# untitled.net
KiCad netlist of a schematic drawn in EAGLE
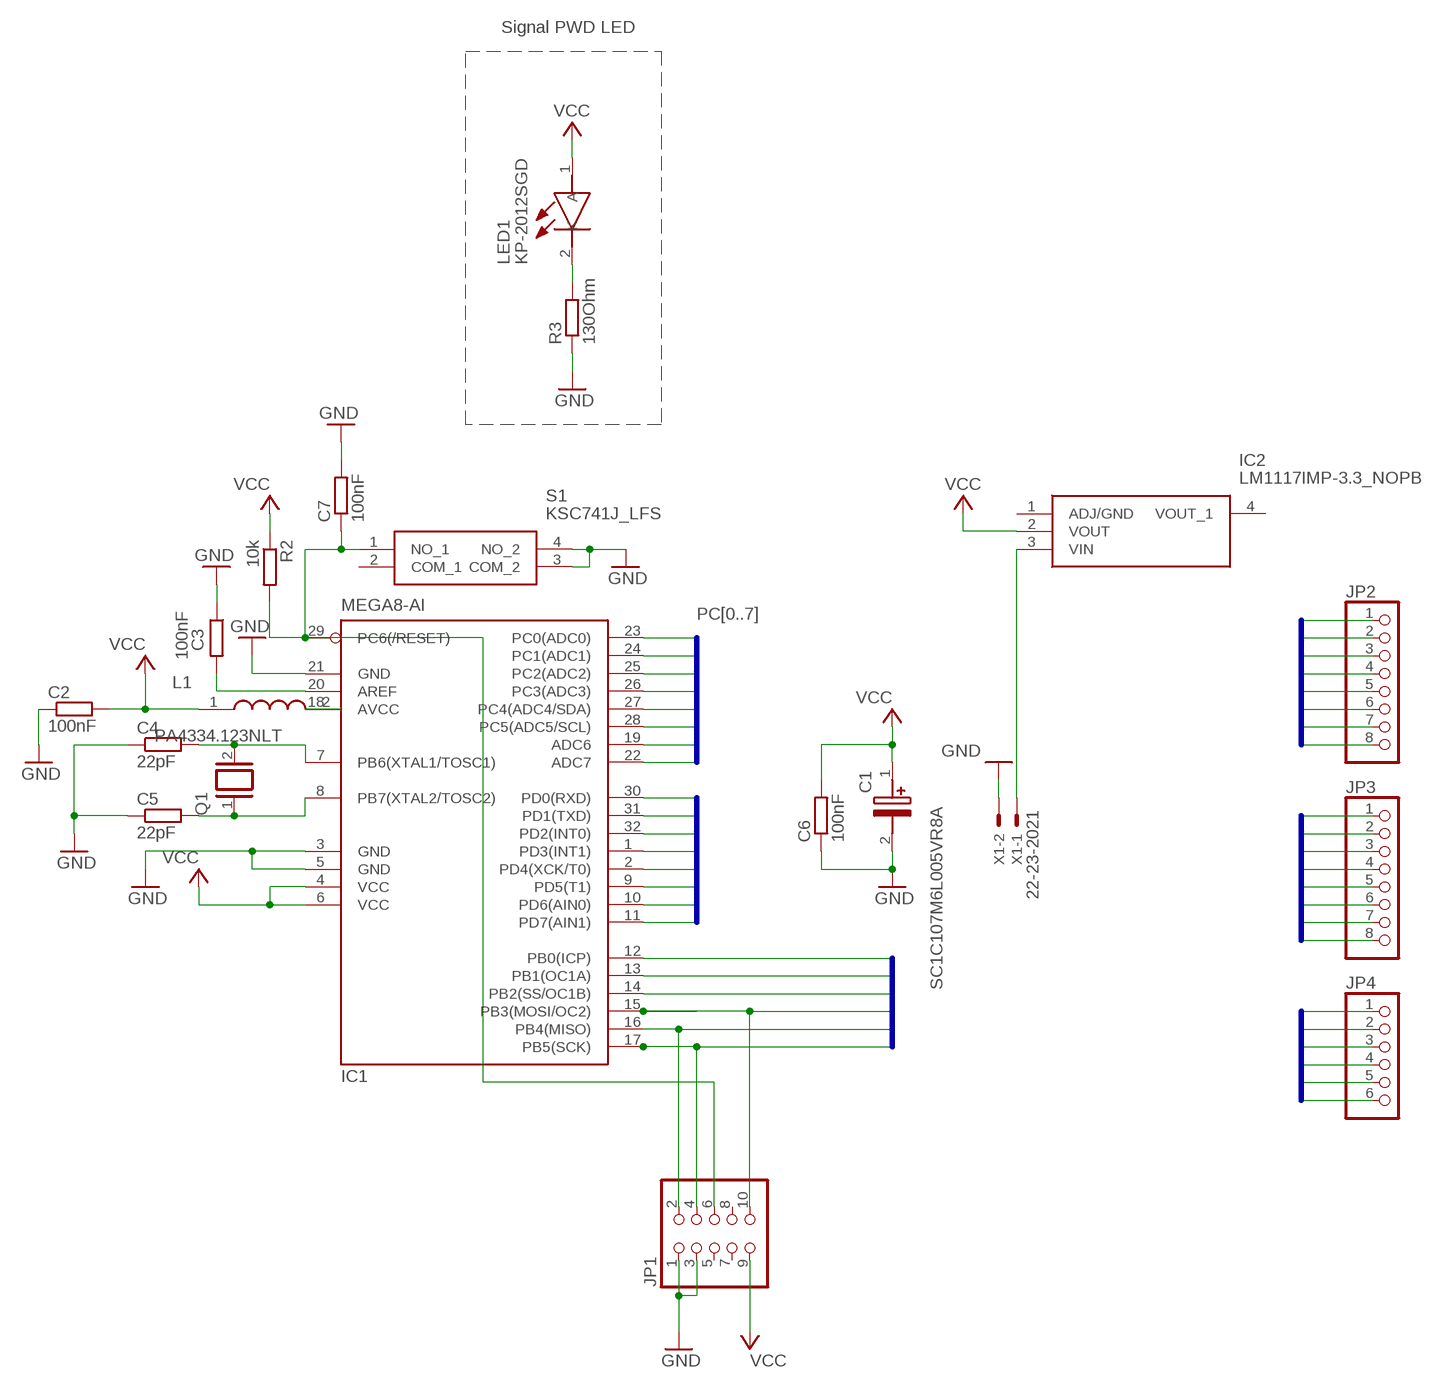
[diagram p0: schematic, sheet 1]

(export (version "E")
  (design (tool "Eeschema 10.0.6"))
  (components
    (comp (ref "C1")
      (value "SC1C107M6L005VR8A")
      (footprint "eagle-import:CAPAE660X560N")
      (libsource (lib "eagle-import") (part "SC1C107M6L005VR8A"))
    )
    (comp (ref "C2")
      (value "100nF")
      (footprint "eagle-import:R0805")
      (libsource (lib "eagle-import") (part "R-EU_R0805"))
    )
    (comp (ref "C3")
      (value "100nF")
      (footprint "eagle-import:R0805")
      (libsource (lib "eagle-import") (part "R-EU_R0805"))
    )
    (comp (ref "C4")
      (value "22pF")
      (footprint "eagle-import:R0805")
      (libsource (lib "eagle-import") (part "R-EU_R0805"))
    )
    (comp (ref "C5")
      (value "22pF")
      (footprint "eagle-import:R0805")
      (libsource (lib "eagle-import") (part "R-EU_R0805"))
    )
    (comp (ref "C6")
      (value "100nF")
      (footprint "eagle-import:R0805")
      (libsource (lib "eagle-import") (part "R-EU_R0805"))
    )
    (comp (ref "C7")
      (value "100nF")
      (footprint "eagle-import:R0805")
      (libsource (lib "eagle-import") (part "R-EU_R0805"))
    )
    (comp (ref "IC1")
      (value "MEGA8-AI")
      (footprint "eagle-import:TQFP32-08")
      (fields (field (name "MPN") "ATMEGA8-16AU"))
      (libsource (lib "eagle-import") (part "MEGA8-AI"))
    )
    (comp (ref "IC2")
      (value "LM1117IMP-3.3_NOPB")
      (footprint "eagle-import:SOT230P700X180-4N")
      (fields
        (field (name "MANUFACTURER_PART_NUMBER") "LM1117IMP-3.3/NOPB")
        (field (name "MOUSER_PART_NUMBER") "926-LM1117IMP3.3NOPB")
        (field (name "RS_PART_NUMBER") "1977198")
      )
      (libsource (lib "eagle-import") (part "LM1117IMP-3.3_NOPB"))
    )
    (comp (ref "JP1")
      (value "PINHD-2X5")
      (footprint "eagle-import:2X05")
      (libsource (lib "eagle-import") (part "PINHD-2X5"))
    )
    (comp (ref "JP2")
      (value "PINHD-1X8")
      (footprint "eagle-import:1X08")
      (libsource (lib "eagle-import") (part "PINHD-1X8"))
    )
    (comp (ref "JP3")
      (value "PINHD-1X8")
      (footprint "eagle-import:1X08")
      (libsource (lib "eagle-import") (part "PINHD-1X8"))
    )
    (comp (ref "JP4")
      (value "PINHD-1X6")
      (footprint "eagle-import:1X06")
      (libsource (lib "eagle-import") (part "PINHD-1X6"))
    )
    (comp (ref "L1")
      (value "PA4334.123NLT")
      (footprint "eagle-import:PA4334123NLT")
      (fields (field (name "MOUSER_PART_NUMBER") "673-PA4334123NLT"))
      (libsource (lib "eagle-import") (part "PA4334.123NLT"))
    )
    (comp (ref "LED1")
      (value "KP-2012SGD")
      (footprint "eagle-import:KP2012SGD")
      (libsource (lib "eagle-import") (part "KP-2012SGD"))
    )
    (comp (ref "Q1")
      (value "XTAL/S")
      (footprint "eagle-import:QS")
      (libsource (lib "eagle-import") (part "XTAL/S"))
    )
    (comp (ref "R2")
      (value "10k")
      (footprint "eagle-import:R0805")
      (libsource (lib "eagle-import") (part "R-EU_R0805"))
    )
    (comp (ref "R3")
      (value "130Ohm")
      (footprint "eagle-import:R0805")
      (libsource (lib "eagle-import") (part "R-EU_R0805"))
    )
    (comp (ref "S1")
      (value "KSC741J_LFS")
      (footprint "eagle-import:KSC821JOLLFS")
      (fields
        (field (name "ARROW_PART_NUMBER") "KSC741J LFS")
        (field (name "MOUSER_PART_NUMBER") "611-KSC741JLFS")
      )
      (libsource (lib "eagle-import") (part "KSC741J_LFS"))
    )
    (comp (ref "X1")
      (value "22-23-2021")
      (footprint "eagle-import:22-23-2021")
      (fields (field (name "MF") "MOLEX"))
      (libsource (lib "eagle-import") (part "22-23-2021"))
    )
  )
  (nets
    (net (code "1") (name "/ADJ{slash}GND") (class "Default")
      (node (ref "IC2") (pin "1") (pinfunction "ADJ/GND_1") (pintype "power_in"))
    )
    (net (code "2") (name "/PB0") (class "Default")
      (node (ref "IC1") (pin "12") (pinfunction "PB0(ICP)_12") (pintype "bidirectional"))
      (node (ref "JP4") (pin "1") (pinfunction "1_1") (pintype "passive"))
    )
    (net (code "3") (name "/PB1") (class "Default")
      (node (ref "IC1") (pin "13") (pinfunction "PB1(OC1A)_13") (pintype "bidirectional"))
      (node (ref "JP4") (pin "2") (pinfunction "2_2") (pintype "passive"))
    )
    (net (code "4") (name "/PB2") (class "Default")
      (node (ref "IC1") (pin "14") (pinfunction "PB2(SS/OC1B)_14") (pintype "bidirectional"))
      (node (ref "JP4") (pin "3") (pinfunction "3_3") (pintype "passive"))
    )
    (net (code "5") (name "/PB3") (class "Default")
      (node (ref "IC1") (pin "15") (pinfunction "PB3(MOSI/OC2)_15") (pintype "bidirectional"))
      (node (ref "JP1") (pin "10") (pinfunction "10_10") (pintype "passive"))
      (node (ref "JP4") (pin "4") (pinfunction "4_4") (pintype "passive"))
    )
    (net (code "6") (name "/PB4") (class "Default")
      (node (ref "IC1") (pin "16") (pinfunction "PB4(MISO)_16") (pintype "bidirectional"))
      (node (ref "JP1") (pin "2") (pinfunction "2_2") (pintype "passive"))
      (node (ref "JP4") (pin "5") (pinfunction "5_5") (pintype "passive"))
    )
    (net (code "7") (name "/PB5") (class "Default")
      (node (ref "IC1") (pin "17") (pinfunction "PB5(SCK)_17") (pintype "bidirectional"))
      (node (ref "JP1") (pin "4") (pinfunction "4_4") (pintype "passive"))
      (node (ref "JP4") (pin "6") (pinfunction "6_6") (pintype "passive"))
    )
    (net (code "8") (name "/PC0") (class "Default")
      (node (ref "IC1") (pin "23") (pinfunction "PC0(ADC0)_23") (pintype "bidirectional"))
      (node (ref "JP2") (pin "1") (pinfunction "1_1") (pintype "passive"))
    )
    (net (code "9") (name "/PC1") (class "Default")
      (node (ref "IC1") (pin "24") (pinfunction "PC1(ADC1)_24") (pintype "bidirectional"))
      (node (ref "JP2") (pin "2") (pinfunction "2_2") (pintype "passive"))
    )
    (net (code "10") (name "/PC2") (class "Default")
      (node (ref "IC1") (pin "25") (pinfunction "PC2(ADC2)_25") (pintype "bidirectional"))
      (node (ref "JP2") (pin "3") (pinfunction "3_3") (pintype "passive"))
    )
    (net (code "11") (name "/PC3") (class "Default")
      (node (ref "IC1") (pin "26") (pinfunction "PC3(ADC3)_26") (pintype "bidirectional"))
      (node (ref "JP2") (pin "4") (pinfunction "4_4") (pintype "passive"))
    )
    (net (code "12") (name "/PC4") (class "Default")
      (node (ref "IC1") (pin "27") (pinfunction "PC4(ADC4/SDA)_27") (pintype "bidirectional"))
      (node (ref "JP2") (pin "5") (pinfunction "5_5") (pintype "passive"))
    )
    (net (code "13") (name "/PC5") (class "Default")
      (node (ref "IC1") (pin "28") (pinfunction "PC5(ADC5/SCL)_28") (pintype "bidirectional"))
      (node (ref "JP2") (pin "6") (pinfunction "6_6") (pintype "passive"))
    )
    (net (code "14") (name "/PC6") (class "Default")
      (node (ref "IC1") (pin "19") (pinfunction "ADC6_19") (pintype "bidirectional"))
      (node (ref "JP2") (pin "7") (pinfunction "7_7") (pintype "passive"))
    )
    (net (code "15") (name "/PC7") (class "Default")
      (node (ref "IC1") (pin "22") (pinfunction "ADC7_22") (pintype "bidirectional"))
      (node (ref "JP2") (pin "8") (pinfunction "8_8") (pintype "passive"))
    )
    (net (code "16") (name "/PD0") (class "Default")
      (node (ref "IC1") (pin "30") (pinfunction "PD0(RXD)_30") (pintype "bidirectional"))
      (node (ref "JP3") (pin "1") (pinfunction "1_1") (pintype "passive"))
    )
    (net (code "17") (name "/PD1") (class "Default")
      (node (ref "IC1") (pin "31") (pinfunction "PD1(TXD)_31") (pintype "bidirectional"))
      (node (ref "JP3") (pin "2") (pinfunction "2_2") (pintype "passive"))
    )
    (net (code "18") (name "/PD2") (class "Default")
      (node (ref "IC1") (pin "32") (pinfunction "PD2(INT0)_32") (pintype "bidirectional"))
      (node (ref "JP3") (pin "3") (pinfunction "3_3") (pintype "passive"))
    )
    (net (code "19") (name "/PD3") (class "Default")
      (node (ref "IC1") (pin "1") (pinfunction "PD3(INT1)_1") (pintype "bidirectional"))
      (node (ref "JP3") (pin "4") (pinfunction "4_4") (pintype "passive"))
    )
    (net (code "20") (name "/PD4") (class "Default")
      (node (ref "IC1") (pin "2") (pinfunction "PD4(XCK/T0)_2") (pintype "bidirectional"))
      (node (ref "JP3") (pin "5") (pinfunction "5_5") (pintype "passive"))
    )
    (net (code "21") (name "/PD5") (class "Default")
      (node (ref "IC1") (pin "9") (pinfunction "PD5(T1)_9") (pintype "bidirectional"))
      (node (ref "JP3") (pin "6") (pinfunction "6_6") (pintype "passive"))
    )
    (net (code "22") (name "/PD6") (class "Default")
      (node (ref "IC1") (pin "10") (pinfunction "PD6(AIN0)_10") (pintype "bidirectional"))
      (node (ref "JP3") (pin "7") (pinfunction "7_7") (pintype "passive"))
    )
    (net (code "23") (name "/PD7") (class "Default")
      (node (ref "IC1") (pin "11") (pinfunction "PD7(AIN1)_11") (pintype "bidirectional"))
      (node (ref "JP3") (pin "8") (pinfunction "8_8") (pintype "passive"))
    )
    (net (code "24") (name "GND") (class "Default")
      (node (ref "C1") (pin "2") (pinfunction "-_2") (pintype "bidirectional"))
      (node (ref "C2") (pin "1") (pinfunction "1_1") (pintype "passive"))
      (node (ref "C3") (pin "1") (pinfunction "1_1") (pintype "passive"))
      (node (ref "C4") (pin "1") (pinfunction "1_1") (pintype "passive"))
      (node (ref "C5") (pin "1") (pinfunction "1_1") (pintype "passive"))
      (node (ref "C6") (pin "1") (pinfunction "1_1") (pintype "passive"))
      (node (ref "C7") (pin "2") (pinfunction "2_2") (pintype "passive"))
      (node (ref "IC1") (pin "21") (pinfunction "GND_21") (pintype "power_in"))
      (node (ref "IC1") (pin "3") (pinfunction "GND_3") (pintype "power_in"))
      (node (ref "IC1") (pin "5") (pinfunction "GND_5") (pintype "power_in"))
      (node (ref "JP1") (pin "1") (pinfunction "1_1") (pintype "passive"))
      (node (ref "JP1") (pin "3") (pinfunction "3_3") (pintype "passive"))
      (node (ref "R3") (pin "1") (pinfunction "1_1") (pintype "passive"))
      (node (ref "S1") (pin "3") (pinfunction "COM_2_3") (pintype "bidirectional"))
      (node (ref "S1") (pin "4") (pinfunction "NO_2_4") (pintype "bidirectional"))
      (node (ref "X1") (pin "2") (pinfunction "S_2") (pintype "passive"))
    )
    (net (code "25") (name "Net-(IC1-AREF)") (class "Default")
      (node (ref "C3") (pin "2") (pinfunction "2_2") (pintype "passive"))
      (node (ref "IC1") (pin "20") (pinfunction "AREF_20") (pintype "passive"))
    )
    (net (code "26") (name "Net-(IC1-AVCC)") (class "Default")
      (node (ref "IC1") (pin "18") (pinfunction "AVCC_18") (pintype "power_in"))
      (node (ref "L1") (pin "2") (pinfunction "2_2") (pintype "bidirectional"))
    )
    (net (code "27") (name "Net-(IC1-PB6(XTAL1{slash}TOSC1))") (class "Default")
      (node (ref "C4") (pin "2") (pinfunction "2_2") (pintype "passive"))
      (node (ref "IC1") (pin "7") (pinfunction "PB6(XTAL1/TOSC1)_7") (pintype "bidirectional"))
      (node (ref "Q1") (pin "2") (pinfunction "2_2") (pintype "passive"))
    )
    (net (code "28") (name "Net-(IC1-PB7(XTAL2{slash}TOSC2))") (class "Default")
      (node (ref "C5") (pin "2") (pinfunction "2_2") (pintype "passive"))
      (node (ref "IC1") (pin "8") (pinfunction "PB7(XTAL2/TOSC2)_8") (pintype "bidirectional"))
      (node (ref "Q1") (pin "1") (pinfunction "1_1") (pintype "passive"))
    )
    (net (code "29") (name "Net-(IC1-PC6({slash}RESET))") (class "Default")
      (node (ref "C7") (pin "1") (pinfunction "1_1") (pintype "passive"))
      (node (ref "IC1") (pin "29") (pinfunction "PC6(/RESET)_29") (pintype "bidirectional"))
      (node (ref "JP1") (pin "6") (pinfunction "6_6") (pintype "passive"))
      (node (ref "R2") (pin "2") (pinfunction "2_2") (pintype "passive"))
      (node (ref "S1") (pin "1") (pinfunction "NO_1_1") (pintype "bidirectional"))
    )
    (net (code "30") (name "Net-(IC2-VIN)") (class "Default")
      (node (ref "IC2") (pin "3") (pinfunction "VIN_3") (pintype "input"))
      (node (ref "X1") (pin "1") (pinfunction "S_1") (pintype "passive"))
    )
    (net (code "31") (name "Net-(LED1-K)") (class "Default")
      (node (ref "LED1") (pin "2") (pinfunction "K_2") (pintype "bidirectional"))
      (node (ref "R3") (pin "2") (pinfunction "2_2") (pintype "passive"))
    )
    (net (code "32") (name "VCC") (class "Default")
      (node (ref "C1") (pin "1") (pinfunction "+_1") (pintype "bidirectional"))
      (node (ref "C2") (pin "2") (pinfunction "2_2") (pintype "passive"))
      (node (ref "C6") (pin "2") (pinfunction "2_2") (pintype "passive"))
      (node (ref "IC1") (pin "4") (pinfunction "VCC_4") (pintype "power_in"))
      (node (ref "IC1") (pin "6") (pinfunction "VCC_6") (pintype "power_in"))
      (node (ref "IC2") (pin "2") (pinfunction "VOUT_2") (pintype "output"))
      (node (ref "JP1") (pin "9") (pinfunction "9_9") (pintype "passive"))
      (node (ref "L1") (pin "1") (pinfunction "1_1") (pintype "bidirectional"))
      (node (ref "LED1") (pin "1") (pinfunction "A_1") (pintype "bidirectional"))
      (node (ref "R2") (pin "1") (pinfunction "1_1") (pintype "passive"))
    )
    (net (code "33") (name "unconnected-(IC2-VOUT_1-Pad4)") (class "Default")
      (node (ref "IC2") (pin "4") (pinfunction "VOUT_1_4") (pintype "output"))
    )
    (net (code "34") (name "unconnected-(JP1-Pad5)") (class "Default")
      (node (ref "JP1") (pin "5") (pinfunction "5_5") (pintype "passive"))
    )
    (net (code "35") (name "unconnected-(JP1-Pad7)") (class "Default")
      (node (ref "JP1") (pin "7") (pinfunction "7_7") (pintype "passive"))
    )
    (net (code "36") (name "unconnected-(JP1-Pad8)") (class "Default")
      (node (ref "JP1") (pin "8") (pinfunction "8_8") (pintype "passive"))
    )
    (net (code "37") (name "unconnected-(S1-COM_1-Pad2)") (class "Default")
      (node (ref "S1") (pin "2") (pinfunction "COM_1_2") (pintype "bidirectional"))
    )
  )
)
